# Measurements.net
KiCad netlist of a schematic drawn in Altium Designer
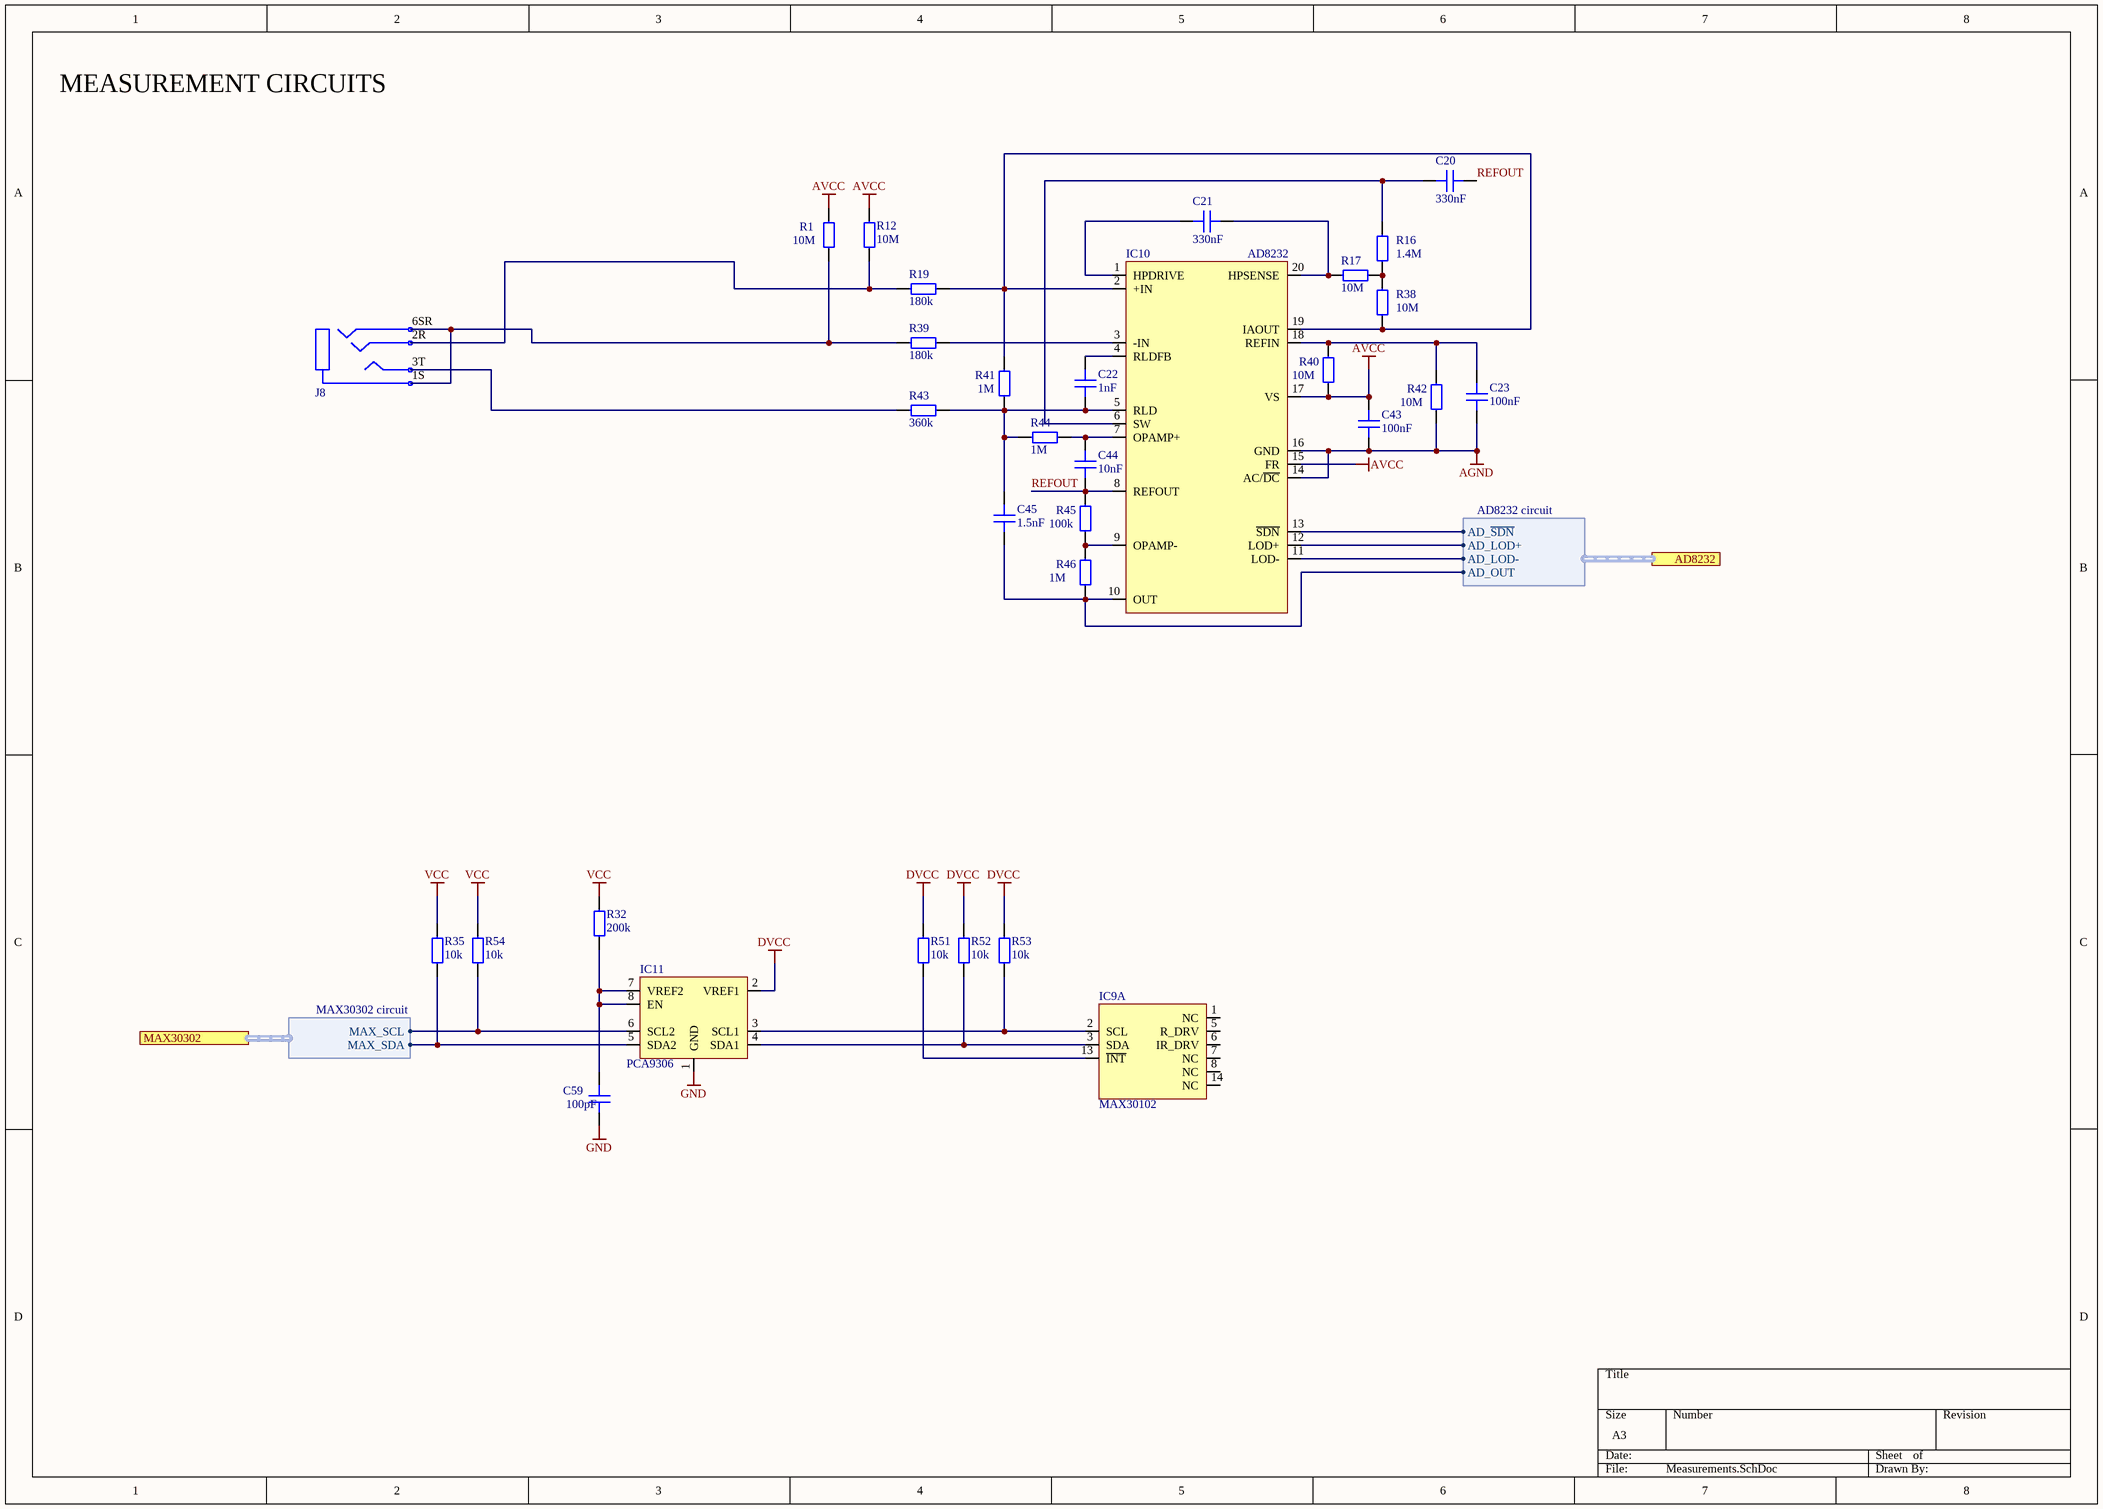
[diagram p0: Measurements.SchDoc]

(export (version "E")
  (design (tool "Eeschema 10.0.6"))
  (components
    (comp (ref "C20")
      (value "330nF")
      (footprint "CAP 0603")
      (description "SMT Capacitor")
      (libsource (lib "Passive") (part "Capacitor"))
    )
    (comp (ref "C21")
      (value "330nF")
      (footprint "CAP 0603")
      (description "SMT Capacitor")
      (libsource (lib "Passive") (part "Capacitor"))
    )
    (comp (ref "C22")
      (value "1nF")
      (footprint "CAP 0603")
      (description "SMT Capacitor")
      (libsource (lib "Passive") (part "Capacitor"))
    )
    (comp (ref "C23")
      (value "100nF")
      (footprint "CAP 0603")
      (description "SMT Capacitor")
      (libsource (lib "Passive") (part "Capacitor"))
    )
    (comp (ref "C43")
      (value "100nF")
      (footprint "CAP 0603")
      (description "SMT Capacitor")
      (libsource (lib "Passive") (part "Capacitor"))
    )
    (comp (ref "C44")
      (value "10nF")
      (footprint "CAP 0603")
      (description "SMT Capacitor")
      (libsource (lib "Passive") (part "Capacitor"))
    )
    (comp (ref "C45")
      (value "1.5nF")
      (footprint "CAP 0603")
      (description "SMT Capacitor")
      (libsource (lib "Passive") (part "Capacitor"))
    )
    (comp (ref "C59")
      (value "100pF")
      (footprint "CAP 0603")
      (description "SMT Capacitor")
      (libsource (lib "Passive") (part "Capacitor"))
    )
    (comp (ref "IC9")
      (value "MAX30102")
      (footprint "MAX30102")
      (description "Pulse Oximeter and Heart-Rate Sensor")
      (libsource (lib "IC") (part "MAX30102"))
    )
    (comp (ref "IC10")
      (value "AD8232")
      (footprint "LFCSP 20")
      (description "Single-Lead, Heart Rate Monitor Front End")
      (libsource (lib "IC") (part "AD8232"))
    )
    (comp (ref "IC11")
      (value "PCA9306")
      (footprint "SSOP8")
      (description "Dual Bidirectional I2C Bus and SMBus Voltage-Level Translator")
      (libsource (lib "IC") (part "PCA9306"))
    )
    (comp (ref "J8")
      (value "4 pin")
      (footprint "CLIFF FC68126")
      (description "Jack 3,5mm, dock, female")
      (libsource (lib "Connectors") (part "CLIFF FC68127 3.5mm"))
    )
    (comp (ref "R1")
      (value "10M")
      (footprint "RES 0603")
      (description "SMDResistor")
      (libsource (lib "Passive") (part "Resistor"))
    )
    (comp (ref "R12")
      (value "10M")
      (footprint "RES 0603")
      (description "SMDResistor")
      (libsource (lib "Passive") (part "Resistor"))
    )
    (comp (ref "R16")
      (value "1.4M")
      (footprint "RES 0603")
      (description "SMDResistor")
      (libsource (lib "Passive") (part "Resistor"))
    )
    (comp (ref "R17")
      (value "10M")
      (footprint "RES 0603")
      (description "SMDResistor")
      (libsource (lib "Passive") (part "Resistor"))
    )
    (comp (ref "R19")
      (value "180k")
      (footprint "RES 0603")
      (description "SMDResistor")
      (libsource (lib "Passive") (part "Resistor"))
    )
    (comp (ref "R32")
      (value "200k")
      (footprint "RES 0603")
      (description "SMDResistor")
      (libsource (lib "Passive") (part "Resistor"))
    )
    (comp (ref "R35")
      (value "10k")
      (footprint "RES 0603")
      (description "SMDResistor")
      (libsource (lib "Passive") (part "Resistor"))
    )
    (comp (ref "R38")
      (value "10M")
      (footprint "RES 0603")
      (description "SMDResistor")
      (libsource (lib "Passive") (part "Resistor"))
    )
    (comp (ref "R39")
      (value "180k")
      (footprint "RES 0603")
      (description "SMDResistor")
      (libsource (lib "Passive") (part "Resistor"))
    )
    (comp (ref "R40")
      (value "10M")
      (footprint "RES 0603")
      (description "SMDResistor")
      (libsource (lib "Passive") (part "Resistor"))
    )
    (comp (ref "R41")
      (value "1M")
      (footprint "RES 0603")
      (description "SMDResistor")
      (libsource (lib "Passive") (part "Resistor"))
    )
    (comp (ref "R42")
      (value "10M")
      (footprint "RES 0603")
      (description "SMDResistor")
      (libsource (lib "Passive") (part "Resistor"))
    )
    (comp (ref "R43")
      (value "360k")
      (footprint "RES 0603")
      (description "SMDResistor")
      (libsource (lib "Passive") (part "Resistor"))
    )
    (comp (ref "R44")
      (value "1M")
      (footprint "RES 0603")
      (description "SMDResistor")
      (libsource (lib "Passive") (part "Resistor"))
    )
    (comp (ref "R45")
      (value "100k")
      (footprint "RES 0603")
      (description "SMDResistor")
      (libsource (lib "Passive") (part "Resistor"))
    )
    (comp (ref "R46")
      (value "1M")
      (footprint "RES 0603")
      (description "SMDResistor")
      (libsource (lib "Passive") (part "Resistor"))
    )
    (comp (ref "R51")
      (value "10k")
      (footprint "RES 0603")
      (description "SMDResistor")
      (libsource (lib "Passive") (part "Resistor"))
    )
    (comp (ref "R52")
      (value "10k")
      (footprint "RES 0603")
      (description "SMDResistor")
      (libsource (lib "Passive") (part "Resistor"))
    )
    (comp (ref "R53")
      (value "10k")
      (footprint "RES 0603")
      (description "SMDResistor")
      (libsource (lib "Passive") (part "Resistor"))
    )
    (comp (ref "R54")
      (value "10k")
      (footprint "RES 0603")
      (description "SMDResistor")
      (libsource (lib "Passive") (part "Resistor"))
    )
  )
  (nets
    (net (code "4") (name "/AD_LOD+") (class "Default")
      (node (ref "IC10") (pin "12") (pinfunction "LOD+_12") (pintype "passive"))
    )
    (net (code "5") (name "/AD_LOD-") (class "Default")
      (node (ref "IC10") (pin "11") (pinfunction "LOD-_11") (pintype "passive"))
    )
    (net (code "6") (name "/AD_OUT") (class "Default")
      (node (ref "C45") (pin "1") (pinfunction "1_1") (pintype "passive"))
      (node (ref "IC10") (pin "10") (pinfunction "OUT_10") (pintype "passive"))
      (node (ref "R46") (pin "1") (pinfunction "1_1") (pintype "passive"))
    )
    (net (code "7") (name "/AD_~{SDN}") (class "Default")
      (node (ref "IC10") (pin "13") (pinfunction "~{SDN}_13") (pintype "passive"))
    )
    (net (code "8") (name "/MAX_SCL") (class "Default")
      (node (ref "IC11") (pin "6") (pinfunction "SCL2_6") (pintype "passive"))
      (node (ref "R54") (pin "1") (pinfunction "1_1") (pintype "passive"))
    )
    (net (code "9") (name "/MAX_SDA") (class "Default")
      (node (ref "IC11") (pin "5") (pinfunction "SDA2_5") (pintype "passive"))
      (node (ref "R35") (pin "1") (pinfunction "1_1") (pintype "passive"))
    )
    (net (code "10") (name "/REFOUT") (class "Default")
      (node (ref "C20") (pin "1") (pinfunction "1_1") (pintype "passive"))
      (node (ref "C44") (pin "1") (pinfunction "1_1") (pintype "passive"))
      (node (ref "IC10") (pin "8") (pinfunction "REFOUT_8") (pintype "passive"))
      (node (ref "R45") (pin "2") (pinfunction "2_2") (pintype "passive"))
    )
    (net (code "13") (name "AGND") (class "Default")
      (node (ref "C23") (pin "1") (pinfunction "1_1") (pintype "passive"))
      (node (ref "C43") (pin "1") (pinfunction "1_1") (pintype "passive"))
      (node (ref "IC10") (pin "14") (pinfunction "AC/~{DC}_14") (pintype "passive"))
      (node (ref "IC10") (pin "16") (pinfunction "GND_16") (pintype "passive"))
      (node (ref "R42") (pin "1") (pinfunction "1_1") (pintype "passive"))
    )
    (net (code "14") (name "AVCC") (class "Default")
      (node (ref "C43") (pin "2") (pinfunction "2_2") (pintype "passive"))
      (node (ref "IC10") (pin "15") (pinfunction "FR_15") (pintype "passive"))
      (node (ref "IC10") (pin "17") (pinfunction "VS_17") (pintype "passive"))
      (node (ref "R1") (pin "2") (pinfunction "2_2") (pintype "passive"))
      (node (ref "R12") (pin "1") (pinfunction "1_1") (pintype "passive"))
      (node (ref "R40") (pin "1") (pinfunction "1_1") (pintype "passive"))
    )
    (net (code "15") (name "DVCC") (class "Default")
      (node (ref "IC11") (pin "2") (pinfunction "VREF1_2") (pintype "passive"))
      (node (ref "R51") (pin "2") (pinfunction "2_2") (pintype "passive"))
      (node (ref "R52") (pin "2") (pinfunction "2_2") (pintype "passive"))
      (node (ref "R53") (pin "2") (pinfunction "2_2") (pintype "passive"))
    )
    (net (code "16") (name "GND") (class "Default")
      (node (ref "C59") (pin "1") (pinfunction "1_1") (pintype "passive"))
      (node (ref "IC11") (pin "1") (pinfunction "GND_1") (pintype "passive"))
    )
    (net (code "17") (name "Net-(IC9A-~{INT})") (class "Default")
      (node (ref "IC9") (pin "13") (pinfunction "~{INT}_13") (pintype "passive"))
      (node (ref "R51") (pin "1") (pinfunction "1_1") (pintype "passive"))
    )
    (net (code "18") (name "Net-(IC10-+IN)") (class "Default")
      (node (ref "IC10") (pin "19") (pinfunction "IAOUT_19") (pintype "passive"))
      (node (ref "IC10") (pin "2") (pinfunction "+IN_2") (pintype "passive"))
      (node (ref "R19") (pin "1") (pinfunction "1_1") (pintype "passive"))
      (node (ref "R38") (pin "1") (pinfunction "1_1") (pintype "passive"))
      (node (ref "R41") (pin "2") (pinfunction "2_2") (pintype "passive"))
    )
    (net (code "19") (name "Net-(IC10--IN)") (class "Default")
      (node (ref "IC10") (pin "3") (pinfunction "-IN_3") (pintype "passive"))
      (node (ref "R39") (pin "1") (pinfunction "1_1") (pintype "passive"))
    )
    (net (code "20") (name "Net-(IC10-HPDRIVE)") (class "Default")
      (node (ref "C21") (pin "2") (pinfunction "2_2") (pintype "passive"))
      (node (ref "IC10") (pin "1") (pinfunction "HPDRIVE_1") (pintype "passive"))
    )
    (net (code "21") (name "Net-(IC10-HPSENSE)") (class "Default")
      (node (ref "C21") (pin "1") (pinfunction "1_1") (pintype "passive"))
      (node (ref "IC10") (pin "20") (pinfunction "HPSENSE_20") (pintype "passive"))
      (node (ref "R17") (pin "2") (pinfunction "2_2") (pintype "passive"))
    )
    (net (code "22") (name "Net-(IC10-OPAMP+)") (class "Default")
      (node (ref "C44") (pin "2") (pinfunction "2_2") (pintype "passive"))
      (node (ref "IC10") (pin "7") (pinfunction "OPAMP+_7") (pintype "passive"))
      (node (ref "R44") (pin "1") (pinfunction "1_1") (pintype "passive"))
    )
    (net (code "23") (name "Net-(IC10-OPAMP-)") (class "Default")
      (node (ref "IC10") (pin "9") (pinfunction "OPAMP-_9") (pintype "passive"))
      (node (ref "R45") (pin "1") (pinfunction "1_1") (pintype "passive"))
      (node (ref "R46") (pin "2") (pinfunction "2_2") (pintype "passive"))
    )
    (net (code "24") (name "Net-(IC10-REFIN)") (class "Default")
      (node (ref "C23") (pin "2") (pinfunction "2_2") (pintype "passive"))
      (node (ref "IC10") (pin "18") (pinfunction "REFIN_18") (pintype "passive"))
      (node (ref "R40") (pin "2") (pinfunction "2_2") (pintype "passive"))
      (node (ref "R42") (pin "2") (pinfunction "2_2") (pintype "passive"))
    )
    (net (code "25") (name "Net-(IC10-RLD)") (class "Default")
      (node (ref "C22") (pin "1") (pinfunction "1_1") (pintype "passive"))
      (node (ref "C45") (pin "2") (pinfunction "2_2") (pintype "passive"))
      (node (ref "IC10") (pin "5") (pinfunction "RLD_5") (pintype "passive"))
      (node (ref "R41") (pin "1") (pinfunction "1_1") (pintype "passive"))
      (node (ref "R43") (pin "1") (pinfunction "1_1") (pintype "passive"))
      (node (ref "R44") (pin "2") (pinfunction "2_2") (pintype "passive"))
    )
    (net (code "26") (name "Net-(IC10-RLDFB)") (class "Default")
      (node (ref "C22") (pin "2") (pinfunction "2_2") (pintype "passive"))
      (node (ref "IC10") (pin "4") (pinfunction "RLDFB_4") (pintype "passive"))
    )
    (net (code "27") (name "Net-(IC10-SW)") (class "Default")
      (node (ref "C20") (pin "2") (pinfunction "2_2") (pintype "passive"))
      (node (ref "IC10") (pin "6") (pinfunction "SW_6") (pintype "passive"))
      (node (ref "R16") (pin "2") (pinfunction "2_2") (pintype "passive"))
    )
    (net (code "28") (name "Net-(IC11-EN)") (class "Default")
      (node (ref "C59") (pin "2") (pinfunction "2_2") (pintype "passive"))
      (node (ref "IC11") (pin "7") (pinfunction "VREF2_7") (pintype "passive"))
      (node (ref "IC11") (pin "8") (pinfunction "EN_8") (pintype "passive"))
      (node (ref "R32") (pin "1") (pinfunction "1_1") (pintype "passive"))
    )
    (net (code "29") (name "Net-(IC11-SCL1)") (class "Default")
      (node (ref "IC11") (pin "3") (pinfunction "SCL1_3") (pintype "passive"))
      (node (ref "IC9") (pin "2") (pinfunction "SCL_2") (pintype "passive"))
      (node (ref "R53") (pin "1") (pinfunction "1_1") (pintype "passive"))
    )
    (net (code "30") (name "Net-(IC11-SDA1)") (class "Default")
      (node (ref "IC11") (pin "4") (pinfunction "SDA1_4") (pintype "passive"))
      (node (ref "IC9") (pin "3") (pinfunction "SDA_3") (pintype "passive"))
      (node (ref "R52") (pin "1") (pinfunction "1_1") (pintype "passive"))
    )
    (net (code "31") (name "Net-(J8-1)") (class "Default")
      (node (ref "J8") (pin "1S") (pinfunction "1_1S") (pintype "passive"))
      (node (ref "J8") (pin "6SR") (pinfunction "6_6SR") (pintype "passive"))
      (node (ref "R1") (pin "1") (pinfunction "1_1") (pintype "passive"))
      (node (ref "R39") (pin "2") (pinfunction "2_2") (pintype "passive"))
    )
    (net (code "32") (name "Net-(J8-2)") (class "Default")
      (node (ref "J8") (pin "2R") (pinfunction "2_2R") (pintype "passive"))
      (node (ref "R12") (pin "2") (pinfunction "2_2") (pintype "passive"))
      (node (ref "R19") (pin "2") (pinfunction "2_2") (pintype "passive"))
    )
    (net (code "33") (name "Net-(J8-3)") (class "Default")
      (node (ref "J8") (pin "3T") (pinfunction "3_3T") (pintype "passive"))
      (node (ref "R43") (pin "2") (pinfunction "2_2") (pintype "passive"))
    )
    (net (code "34") (name "Net-(R16-Pad1)") (class "Default")
      (node (ref "R16") (pin "1") (pinfunction "1_1") (pintype "passive"))
      (node (ref "R17") (pin "1") (pinfunction "1_1") (pintype "passive"))
      (node (ref "R38") (pin "2") (pinfunction "2_2") (pintype "passive"))
    )
    (net (code "35") (name "VCC") (class "Default")
      (node (ref "R32") (pin "2") (pinfunction "2_2") (pintype "passive"))
      (node (ref "R35") (pin "2") (pinfunction "2_2") (pintype "passive"))
      (node (ref "R54") (pin "2") (pinfunction "2_2") (pintype "passive"))
    )
    (net (code "36") (name "unconnected-(IC9A-IR_DRV-Pad6)") (class "Default")
      (node (ref "IC9") (pin "6") (pinfunction "IR_DRV_6") (pintype "passive"))
    )
    (net (code "37") (name "unconnected-(IC9A-NC-Pad1)") (class "Default")
      (node (ref "IC9") (pin "1") (pinfunction "NC_1") (pintype "passive"))
    )
    (net (code "38") (name "unconnected-(IC9A-NC-Pad7)") (class "Default")
      (node (ref "IC9") (pin "7") (pinfunction "NC_7") (pintype "passive"))
    )
    (net (code "39") (name "unconnected-(IC9A-NC-Pad8)") (class "Default")
      (node (ref "IC9") (pin "8") (pinfunction "NC_8") (pintype "passive"))
    )
    (net (code "40") (name "unconnected-(IC9A-NC-Pad14)") (class "Default")
      (node (ref "IC9") (pin "14") (pinfunction "NC_14") (pintype "passive"))
    )
    (net (code "41") (name "unconnected-(IC9A-R_DRV-Pad5)") (class "Default")
      (node (ref "IC9") (pin "5") (pinfunction "R_DRV_5") (pintype "passive"))
    )
  )
)
